# artlight.net
KiCad netlist of a schematic drawn in EAGLE
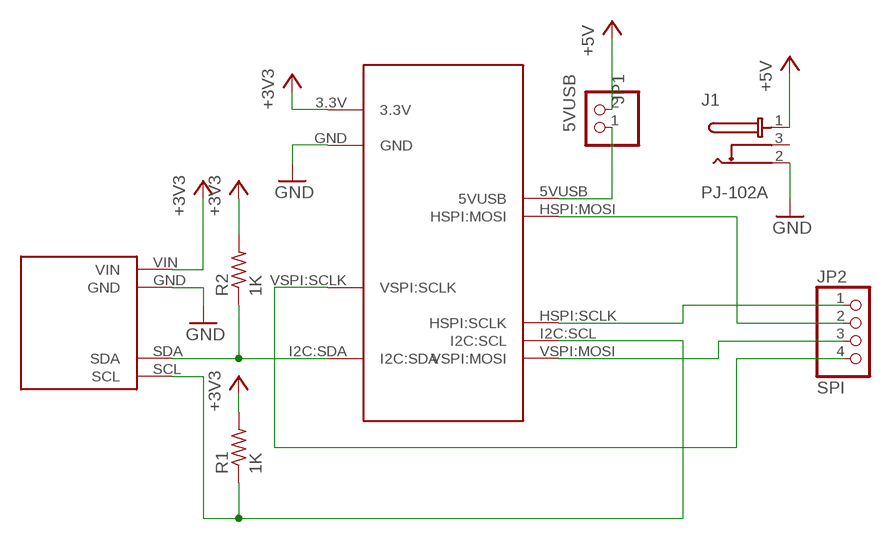
[diagram p0: schematic, sheet 1]

(export (version "E")
  (design (tool "Eeschema 10.0.6"))
  (components
    (comp (ref "J1")
      (value "PJ-102A")
      (footprint "eagle-import:CUI_PJ-102A")
      (fields (field (name "MANUFACTURER") "CUI inc") (field (name "MF") "CUI"))
      (libsource (lib "eagle-import") (part "PJ-102A"))
    )
    (comp (ref "JP1")
      (value "5VUSB")
      (footprint "eagle-import:1X02_90")
      (libsource (lib "eagle-import") (part "PINHD-1X2/90"))
    )
    (comp (ref "JP2")
      (value "SPI")
      (footprint "eagle-import:1X04_90")
      (libsource (lib "eagle-import") (part "PINHD-1X4/90"))
    )
    (comp (ref "R1")
      (value "1K")
      (footprint "eagle-import:0204_7")
      (libsource (lib "eagle-import") (part "R-US_0204/7"))
    )
    (comp (ref "R2")
      (value "1K")
      (footprint "eagle-import:0204_7")
      (libsource (lib "eagle-import") (part "R-US_0204/7"))
    )
    (comp (ref "U$1")
      (value "HUZZAH32-ARTLIGHT")
      (footprint "eagle-import:FEATHERWING-ARTLIGHT")
      (libsource (lib "eagle-import") (part "HUZZAH32-ARTLIGHT"))
    )
    (comp (ref "U$3")
      (value "TSL2561-ARTLIGHT")
      (footprint "eagle-import:TSL2561-ARTLIGHT")
      (libsource (lib "eagle-import") (part "TSL2561-ARTLIGHT"))
    )
  )
  (nets
    (net (code "1") (name "+3V3") (class "Default")
      (node (ref "R1") (pin "2") (pinfunction "2_2") (pintype "passive"))
      (node (ref "R2") (pin "2") (pinfunction "2_2") (pintype "passive"))
      (node (ref "U$1") (pin "3.3V") (pinfunction "3.3V_3.3V") (pintype "bidirectional"))
      (node (ref "U$3") (pin "VIN") (pinfunction "VIN_VIN") (pintype "bidirectional"))
    )
    (net (code "2") (name "+5V") (class "Default")
      (node (ref "J1") (pin "1") (pinfunction "1_1") (pintype "power_in"))
      (node (ref "JP1") (pin "2") (pinfunction "2_2") (pintype "passive"))
    )
    (net (code "3") (name "/3") (class "Default")
      (node (ref "J1") (pin "3") (pinfunction "3_3") (pintype "power_in"))
    )
    (net (code "4") (name "GND") (class "Default")
      (node (ref "J1") (pin "2") (pinfunction "2_2") (pintype "power_in"))
      (node (ref "U$1") (pin "GND") (pinfunction "GND_GND") (pintype "bidirectional"))
      (node (ref "U$3") (pin "GND") (pinfunction "GND_GND") (pintype "bidirectional"))
    )
    (net (code "5") (name "Net-(JP1-Pad1)") (class "Default")
      (node (ref "JP1") (pin "1") (pinfunction "1_1") (pintype "passive"))
      (node (ref "U$1") (pin "5VUSB") (pinfunction "5VUSB_5VUSB") (pintype "bidirectional"))
    )
    (net (code "6") (name "Net-(JP2-Pad1)") (class "Default")
      (node (ref "JP2") (pin "1") (pinfunction "1_1") (pintype "passive"))
      (node (ref "U$1") (pin "HSPI:SCLK") (pinfunction "HSPI:SCLK_HSPI:SCLK") (pintype "bidirectional"))
    )
    (net (code "7") (name "Net-(JP2-Pad2)") (class "Default")
      (node (ref "JP2") (pin "2") (pinfunction "2_2") (pintype "passive"))
      (node (ref "U$1") (pin "HSPI:MOSI") (pinfunction "HSPI:MOSI_HSPI:MOSI") (pintype "bidirectional"))
    )
    (net (code "8") (name "Net-(JP2-Pad3)") (class "Default")
      (node (ref "JP2") (pin "3") (pinfunction "3_3") (pintype "passive"))
      (node (ref "U$1") (pin "VSPI:MOSI") (pinfunction "VSPI:MOSI_VSPI:MOSI") (pintype "bidirectional"))
    )
    (net (code "9") (name "Net-(JP2-Pad4)") (class "Default")
      (node (ref "JP2") (pin "4") (pinfunction "4_4") (pintype "passive"))
      (node (ref "U$1") (pin "VSPI:SCLK") (pinfunction "VSPI:SCLK_VSPI:SCLK") (pintype "bidirectional"))
    )
    (net (code "10") (name "Net-(R1-Pad1)") (class "Default")
      (node (ref "R1") (pin "1") (pinfunction "1_1") (pintype "passive"))
      (node (ref "U$1") (pin "I2C:SCL") (pinfunction "I2C:SCL_I2C:SCL") (pintype "bidirectional"))
      (node (ref "U$3") (pin "SCL") (pinfunction "SCL_SCL") (pintype "bidirectional"))
    )
    (net (code "11") (name "Net-(R2-Pad1)") (class "Default")
      (node (ref "R2") (pin "1") (pinfunction "1_1") (pintype "passive"))
      (node (ref "U$1") (pin "I2C:SDA") (pinfunction "I2C:SDA_I2C:SDA") (pintype "bidirectional"))
      (node (ref "U$3") (pin "SDA") (pinfunction "SDA_SDA") (pintype "bidirectional"))
    )
  )
)
